# brobotESP12.net
KiCad netlist of a schematic drawn in EAGLE
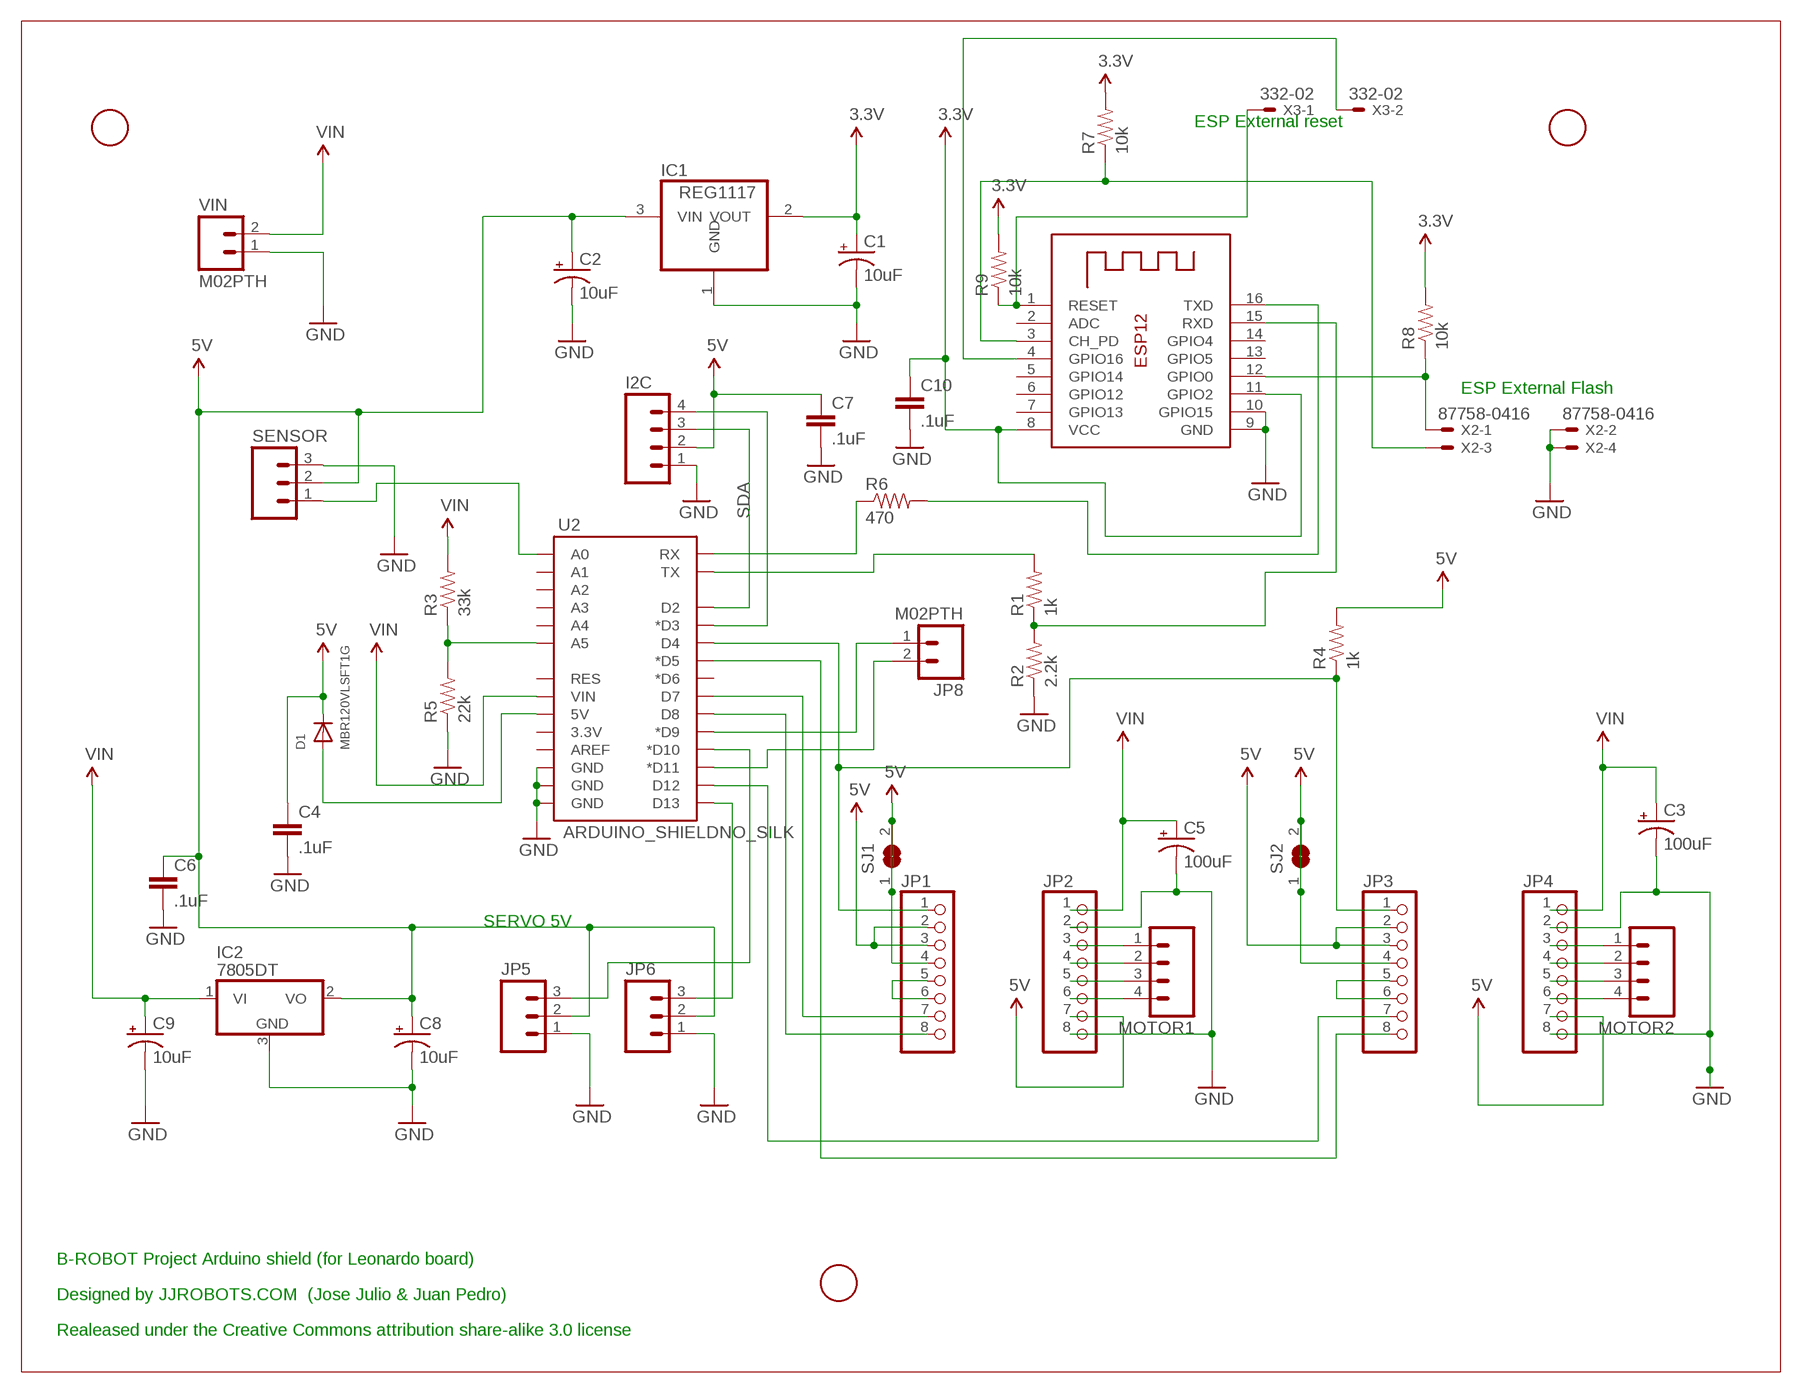
[diagram p0: schematic, sheet 1]

(export (version "E")
  (design (tool "Eeschema 10.0.6"))
  (components
    (comp (ref "C1")
      (value "10uF")
      (footprint "eagle-import:EIA3216")
      (libsource (lib "eagle-import") (part "CAP_POL1206"))
    )
    (comp (ref "C2")
      (value "10uF")
      (footprint "eagle-import:EIA3216")
      (libsource (lib "eagle-import") (part "CAP_POL1206"))
    )
    (comp (ref "C3")
      (value "100uF")
      (footprint "eagle-import:PANASONIC_D")
      (libsource (lib "eagle-import") (part "CAP_POLD"))
    )
    (comp (ref "C4")
      (value ".1uF")
      (footprint "eagle-import:0402-CAP")
      (libsource (lib "eagle-import") (part "CAP0402-CAP"))
    )
    (comp (ref "C5")
      (value "100uF")
      (footprint "eagle-import:PANASONIC_D")
      (libsource (lib "eagle-import") (part "CAP_POLD"))
    )
    (comp (ref "C6")
      (value ".1uF")
      (footprint "eagle-import:0402-CAP")
      (libsource (lib "eagle-import") (part "CAP0402-CAP"))
    )
    (comp (ref "C7")
      (value ".1uF")
      (footprint "eagle-import:0402-CAP")
      (libsource (lib "eagle-import") (part "CAP0402-CAP"))
    )
    (comp (ref "C8")
      (value "10uF")
      (footprint "eagle-import:EIA3216")
      (libsource (lib "eagle-import") (part "CAP_POL1206"))
    )
    (comp (ref "C9")
      (value "10uF")
      (footprint "eagle-import:EIA3216")
      (libsource (lib "eagle-import") (part "CAP_POL1206"))
    )
    (comp (ref "C10")
      (value ".1uF")
      (footprint "eagle-import:0402-CAP")
      (libsource (lib "eagle-import") (part "CAP0402-CAP"))
    )
    (comp (ref "D1")
      (value "MBR120VLSFT1G")
      (footprint "eagle-import:SOD-123")
      (libsource (lib "eagle-import") (part "DIODESOD-123"))
    )
    (comp (ref "I2C")
      (value "M04PTH")
      (footprint "eagle-import:1X04")
      (libsource (lib "eagle-import") (part "M04PTH"))
    )
    (comp (ref "IC1")
      (value "REG1117")
      (footprint "eagle-import:SOT223")
      (libsource (lib "eagle-import") (part "REG1117"))
    )
    (comp (ref "IC2")
      (value "7805DT")
      (footprint "eagle-import:TO252")
      (libsource (lib "eagle-import") (part "78DT05"))
    )
    (comp (ref "JP1")
      (value "PINHD-1X8")
      (footprint "eagle-import:1X08")
      (libsource (lib "eagle-import") (part "PINHD-1X8"))
    )
    (comp (ref "JP2")
      (value "PINHD-1X8")
      (footprint "eagle-import:1X08")
      (libsource (lib "eagle-import") (part "PINHD-1X8"))
    )
    (comp (ref "JP3")
      (value "PINHD-1X8")
      (footprint "eagle-import:1X08")
      (libsource (lib "eagle-import") (part "PINHD-1X8"))
    )
    (comp (ref "JP4")
      (value "PINHD-1X8")
      (footprint "eagle-import:1X08")
      (libsource (lib "eagle-import") (part "PINHD-1X8"))
    )
    (comp (ref "JP5")
      (value "M03PTH")
      (footprint "eagle-import:1X03")
      (libsource (lib "eagle-import") (part "M03PTH"))
    )
    (comp (ref "JP6")
      (value "M03PTH")
      (footprint "eagle-import:1X03")
      (libsource (lib "eagle-import") (part "M03PTH"))
    )
    (comp (ref "JP8")
      (value "M02PTH")
      (footprint "eagle-import:1X02")
      (libsource (lib "eagle-import") (part "M02PTH"))
    )
    (comp (ref "MOTOR1")
      (value "M04PTH")
      (footprint "eagle-import:1X04")
      (libsource (lib "eagle-import") (part "M04PTH"))
    )
    (comp (ref "MOTOR2")
      (value "M04PTH")
      (footprint "eagle-import:1X04")
      (libsource (lib "eagle-import") (part "M04PTH"))
    )
    (comp (ref "R1")
      (value "1k")
      (footprint "eagle-import:0805")
      (libsource (lib "eagle-import") (part "RESISTOR0805-RES"))
    )
    (comp (ref "R2")
      (value "2.2k")
      (footprint "eagle-import:0805")
      (libsource (lib "eagle-import") (part "RESISTOR0805-RES"))
    )
    (comp (ref "R3")
      (value "33k")
      (footprint "eagle-import:0805")
      (libsource (lib "eagle-import") (part "RESISTOR0805-RES"))
    )
    (comp (ref "R4")
      (value "1k")
      (footprint "eagle-import:0805")
      (libsource (lib "eagle-import") (part "RESISTOR0805-RES"))
    )
    (comp (ref "R5")
      (value "22k")
      (footprint "eagle-import:0805")
      (libsource (lib "eagle-import") (part "RESISTOR0805-RES"))
    )
    (comp (ref "R6")
      (value "470")
      (footprint "eagle-import:0805")
      (libsource (lib "eagle-import") (part "RESISTOR0805-RES"))
    )
    (comp (ref "R7")
      (value "10k")
      (footprint "eagle-import:0805")
      (libsource (lib "eagle-import") (part "RESISTOR0805-RES"))
    )
    (comp (ref "R8")
      (value "10k")
      (footprint "eagle-import:0805")
      (libsource (lib "eagle-import") (part "RESISTOR0805-RES"))
    )
    (comp (ref "R9")
      (value "10k")
      (footprint "eagle-import:0805")
      (libsource (lib "eagle-import") (part "RESISTOR0805-RES"))
    )
    (comp (ref "SENSOR")
      (value "M03PTH")
      (footprint "eagle-import:1X03")
      (libsource (lib "eagle-import") (part "M03PTH"))
    )
    (comp (ref "SJ1")
      (value "SJW")
      (footprint "eagle-import:SJW")
      (libsource (lib "eagle-import") (part "SJW"))
    )
    (comp (ref "SJ2")
      (value "SJW")
      (footprint "eagle-import:SJW")
      (libsource (lib "eagle-import") (part "SJW"))
    )
    (comp (ref "U$1")
      (value "FIDUCIAL")
      (footprint "eagle-import:FIDUCIAL_1MM")
      (libsource (lib "eagle-import") (part "FIDUCIAL"))
    )
    (comp (ref "U$2")
      (value "FIDUCIAL")
      (footprint "eagle-import:FIDUCIAL_1MM")
      (libsource (lib "eagle-import") (part "FIDUCIAL"))
    )
    (comp (ref "U$3")
      (value "FIDUCIAL")
      (footprint "eagle-import:FIDUCIAL_1MM")
      (libsource (lib "eagle-import") (part "FIDUCIAL"))
    )
    (comp (ref "U2")
      (value "ARDUINO_SHIELDNO_SILK")
      (footprint "eagle-import:DUEMILANOVE_VIAS")
      (libsource (lib "eagle-import") (part "ARDUINO_SHIELDNO_SILK"))
    )
    (comp (ref "VIN")
      (value "M02PTH")
      (footprint "eagle-import:1X02")
      (libsource (lib "eagle-import") (part "M02PTH"))
    )
    (comp (ref "X1")
      (value "ESP-12")
      (footprint "eagle-import:ESP-12")
      (libsource (lib "eagle-import") (part "ESP-12"))
    )
    (comp (ref "X2")
      (value "87758-0416")
      (footprint "eagle-import:87758-0416")
      (fields (field (name "MF") "FARNELL"))
      (libsource (lib "eagle-import") (part "87758-0416"))
    )
    (comp (ref "X3")
      (value "332-02")
      (footprint "eagle-import:332-02")
      (libsource (lib "eagle-import") (part "332-02"))
    )
  )
  (nets
    (net (code "1") (name "/SDA") (class "Default")
      (node (ref "I2C") (pin "3") (pinfunction "3_3") (pintype "passive"))
      (node (ref "U2") (pin "D2") (pinfunction "D2_D2") (pintype "bidirectional"))
    )
    (net (code "2") (name "3.3V") (class "Default")
      (node (ref "C1") (pin "A") (pinfunction "+_A") (pintype "passive"))
      (node (ref "C10") (pin "1") (pinfunction "1_1") (pintype "passive"))
      (node (ref "IC1") (pin "2") (pinfunction "VOUT_2") (pintype "output"))
      (node (ref "R7") (pin "2") (pinfunction "2_2") (pintype "passive"))
      (node (ref "R8") (pin "2") (pinfunction "2_2") (pintype "passive"))
      (node (ref "R9") (pin "2") (pinfunction "2_2") (pintype "passive"))
      (node (ref "X1") (pin "11") (pinfunction "GPIO2_11") (pintype "bidirectional"))
      (node (ref "X1") (pin "8") (pinfunction "VCC_8") (pintype "power_in"))
    )
    (net (code "3") (name "5V") (class "Default")
      (node (ref "C2") (pin "A") (pinfunction "+_A") (pintype "passive"))
      (node (ref "C4") (pin "1") (pinfunction "1_1") (pintype "passive"))
      (node (ref "C6") (pin "1") (pinfunction "1_1") (pintype "passive"))
      (node (ref "C7") (pin "1") (pinfunction "1_1") (pintype "passive"))
      (node (ref "C8") (pin "A") (pinfunction "+_A") (pintype "passive"))
      (node (ref "D1") (pin "C") (pinfunction "C_C") (pintype "passive"))
      (node (ref "I2C") (pin "2") (pinfunction "2_2") (pintype "passive"))
      (node (ref "IC1") (pin "3") (pinfunction "VIN_3") (pintype "input"))
      (node (ref "IC2") (pin "2") (pinfunction "VO_2") (pintype "passive"))
      (node (ref "JP1") (pin "2") (pinfunction "2_2") (pintype "passive"))
      (node (ref "JP1") (pin "3") (pinfunction "3_3") (pintype "passive"))
      (node (ref "JP1") (pin "4") (pinfunction "4_4") (pintype "passive"))
      (node (ref "JP2") (pin "7") (pinfunction "7_7") (pintype "passive"))
      (node (ref "JP3") (pin "2") (pinfunction "2_2") (pintype "passive"))
      (node (ref "JP3") (pin "3") (pinfunction "3_3") (pintype "passive"))
      (node (ref "JP3") (pin "4") (pinfunction "4_4") (pintype "passive"))
      (node (ref "JP4") (pin "7") (pinfunction "7_7") (pintype "passive"))
      (node (ref "JP5") (pin "2") (pinfunction "2_2") (pintype "passive"))
      (node (ref "JP6") (pin "2") (pinfunction "2_2") (pintype "passive"))
      (node (ref "R4") (pin "2") (pinfunction "2_2") (pintype "passive"))
      (node (ref "SENSOR") (pin "2") (pinfunction "2_2") (pintype "passive"))
      (node (ref "SJ1") (pin "1") (pinfunction "1_1") (pintype "passive"))
      (node (ref "SJ1") (pin "2") (pinfunction "2_2") (pintype "passive"))
      (node (ref "SJ2") (pin "1") (pinfunction "1_1") (pintype "passive"))
      (node (ref "SJ2") (pin "2") (pinfunction "2_2") (pintype "passive"))
    )
    (net (code "4") (name "GND") (class "Default")
      (node (ref "C1") (pin "C") (pinfunction "-_C") (pintype "passive"))
      (node (ref "C10") (pin "2") (pinfunction "2_2") (pintype "passive"))
      (node (ref "C2") (pin "C") (pinfunction "-_C") (pintype "passive"))
      (node (ref "C3") (pin "-") (pinfunction "-_-") (pintype "passive"))
      (node (ref "C4") (pin "2") (pinfunction "2_2") (pintype "passive"))
      (node (ref "C5") (pin "-") (pinfunction "-_-") (pintype "passive"))
      (node (ref "C6") (pin "2") (pinfunction "2_2") (pintype "passive"))
      (node (ref "C7") (pin "2") (pinfunction "2_2") (pintype "passive"))
      (node (ref "C8") (pin "C") (pinfunction "-_C") (pintype "passive"))
      (node (ref "C9") (pin "C") (pinfunction "-_C") (pintype "passive"))
      (node (ref "I2C") (pin "1") (pinfunction "1_1") (pintype "passive"))
      (node (ref "IC1") (pin "1") (pinfunction "GND_1") (pintype "power_in"))
      (node (ref "IC2") (pin "3") (pinfunction "GND_3") (pintype "passive"))
      (node (ref "JP2") (pin "2") (pinfunction "2_2") (pintype "passive"))
      (node (ref "JP2") (pin "8") (pinfunction "8_8") (pintype "passive"))
      (node (ref "JP4") (pin "2") (pinfunction "2_2") (pintype "passive"))
      (node (ref "JP4") (pin "8") (pinfunction "8_8") (pintype "passive"))
      (node (ref "JP5") (pin "1") (pinfunction "1_1") (pintype "passive"))
      (node (ref "JP6") (pin "1") (pinfunction "1_1") (pintype "passive"))
      (node (ref "R2") (pin "1") (pinfunction "1_1") (pintype "passive"))
      (node (ref "R5") (pin "1") (pinfunction "1_1") (pintype "passive"))
      (node (ref "SENSOR") (pin "3") (pinfunction "3_3") (pintype "passive"))
      (node (ref "U2") (pin "GND@0") (pinfunction "GND_GND@0") (pintype "bidirectional"))
      (node (ref "U2") (pin "GND@1") (pinfunction "GND_GND@1") (pintype "bidirectional"))
      (node (ref "U2") (pin "GND@2") (pinfunction "GND_GND@2") (pintype "bidirectional"))
      (node (ref "VIN") (pin "1") (pinfunction "1_1") (pintype "passive"))
      (node (ref "X1") (pin "10") (pinfunction "GPIO15_10") (pintype "bidirectional"))
      (node (ref "X1") (pin "9") (pinfunction "GND_9") (pintype "power_in"))
      (node (ref "X2") (pin "2") (pinfunction "S_2") (pintype "passive"))
      (node (ref "X2") (pin "4") (pinfunction "S_4") (pintype "passive"))
    )
    (net (code "5") (name "Net-(D1-PadA)") (class "Default")
      (node (ref "D1") (pin "A") (pinfunction "A_A") (pintype "passive"))
      (node (ref "U2") (pin "5V") (pinfunction "5V_5V") (pintype "bidirectional"))
    )
    (net (code "6") (name "Net-(JP1-Pad1)") (class "Default")
      (node (ref "JP1") (pin "1") (pinfunction "1_1") (pintype "passive"))
      (node (ref "JP3") (pin "1") (pinfunction "1_1") (pintype "passive"))
      (node (ref "R4") (pin "1") (pinfunction "1_1") (pintype "passive"))
      (node (ref "U2") (pin "D4") (pinfunction "D4_D4") (pintype "bidirectional"))
    )
    (net (code "7") (name "Net-(JP1-Pad5)") (class "Default")
      (node (ref "JP1") (pin "5") (pinfunction "5_5") (pintype "passive"))
      (node (ref "JP1") (pin "6") (pinfunction "6_6") (pintype "passive"))
    )
    (net (code "8") (name "Net-(JP1-Pad7)") (class "Default")
      (node (ref "JP1") (pin "7") (pinfunction "7_7") (pintype "passive"))
      (node (ref "U2") (pin "D7") (pinfunction "D7_D7") (pintype "bidirectional"))
    )
    (net (code "9") (name "Net-(JP1-Pad8)") (class "Default")
      (node (ref "JP1") (pin "8") (pinfunction "8_8") (pintype "passive"))
      (node (ref "U2") (pin "D8") (pinfunction "D8_D8") (pintype "bidirectional"))
    )
    (net (code "10") (name "Net-(JP2-Pad3)") (class "Default")
      (node (ref "JP2") (pin "3") (pinfunction "3_3") (pintype "passive"))
      (node (ref "MOTOR1") (pin "1") (pinfunction "1_1") (pintype "passive"))
    )
    (net (code "11") (name "Net-(JP2-Pad4)") (class "Default")
      (node (ref "JP2") (pin "4") (pinfunction "4_4") (pintype "passive"))
      (node (ref "MOTOR1") (pin "2") (pinfunction "2_2") (pintype "passive"))
    )
    (net (code "12") (name "Net-(JP2-Pad5)") (class "Default")
      (node (ref "JP2") (pin "5") (pinfunction "5_5") (pintype "passive"))
      (node (ref "MOTOR1") (pin "3") (pinfunction "3_3") (pintype "passive"))
    )
    (net (code "13") (name "Net-(JP2-Pad6)") (class "Default")
      (node (ref "JP2") (pin "6") (pinfunction "6_6") (pintype "passive"))
      (node (ref "MOTOR1") (pin "4") (pinfunction "4_4") (pintype "passive"))
    )
    (net (code "14") (name "Net-(JP3-Pad5)") (class "Default")
      (node (ref "JP3") (pin "5") (pinfunction "5_5") (pintype "passive"))
      (node (ref "JP3") (pin "6") (pinfunction "6_6") (pintype "passive"))
    )
    (net (code "15") (name "Net-(JP3-Pad7)") (class "Default")
      (node (ref "JP3") (pin "7") (pinfunction "7_7") (pintype "passive"))
      (node (ref "U2") (pin "D12") (pinfunction "D12_D12") (pintype "bidirectional"))
    )
    (net (code "16") (name "Net-(JP4-Pad3)") (class "Default")
      (node (ref "JP4") (pin "3") (pinfunction "3_3") (pintype "passive"))
      (node (ref "MOTOR2") (pin "1") (pinfunction "1_1") (pintype "passive"))
    )
    (net (code "17") (name "Net-(JP4-Pad4)") (class "Default")
      (node (ref "JP4") (pin "4") (pinfunction "4_4") (pintype "passive"))
      (node (ref "MOTOR2") (pin "2") (pinfunction "2_2") (pintype "passive"))
    )
    (net (code "18") (name "Net-(JP4-Pad5)") (class "Default")
      (node (ref "JP4") (pin "5") (pinfunction "5_5") (pintype "passive"))
      (node (ref "MOTOR2") (pin "3") (pinfunction "3_3") (pintype "passive"))
    )
    (net (code "19") (name "Net-(JP4-Pad6)") (class "Default")
      (node (ref "JP4") (pin "6") (pinfunction "6_6") (pintype "passive"))
      (node (ref "MOTOR2") (pin "4") (pinfunction "4_4") (pintype "passive"))
    )
    (net (code "20") (name "Net-(JP6-Pad3)") (class "Default")
      (node (ref "JP6") (pin "3") (pinfunction "3_3") (pintype "passive"))
      (node (ref "U2") (pin "D13") (pinfunction "D13_D13") (pintype "bidirectional"))
    )
    (net (code "21") (name "Net-(R1-Pad2)") (class "Default")
      (node (ref "R1") (pin "2") (pinfunction "2_2") (pintype "passive"))
      (node (ref "U2") (pin "TX") (pinfunction "TX_TX") (pintype "bidirectional"))
    )
    (net (code "22") (name "Net-(R3-Pad1)") (class "Default")
      (node (ref "R3") (pin "1") (pinfunction "1_1") (pintype "passive"))
      (node (ref "R5") (pin "2") (pinfunction "2_2") (pintype "passive"))
      (node (ref "U2") (pin "A5") (pinfunction "A5_A5") (pintype "bidirectional"))
    )
    (net (code "23") (name "Net-(R6-Pad1)") (class "Default")
      (node (ref "R6") (pin "1") (pinfunction "1_1") (pintype "passive"))
      (node (ref "U2") (pin "RX") (pinfunction "RX_RX") (pintype "bidirectional"))
    )
    (net (code "24") (name "Net-(SENSOR-Pad1)") (class "Default")
      (node (ref "SENSOR") (pin "1") (pinfunction "1_1") (pintype "passive"))
      (node (ref "U2") (pin "A0") (pinfunction "A0_A0") (pintype "bidirectional"))
    )
    (net (code "25") (name "Net-(U2-*D3)") (class "Default")
      (node (ref "I2C") (pin "4") (pinfunction "4_4") (pintype "passive"))
      (node (ref "U2") (pin "D3") (pinfunction "*D3_D3") (pintype "bidirectional"))
    )
    (net (code "26") (name "Net-(U2-*D5)") (class "Default")
      (node (ref "JP3") (pin "8") (pinfunction "8_8") (pintype "passive"))
      (node (ref "U2") (pin "D5") (pinfunction "*D5_D5") (pintype "bidirectional"))
    )
    (net (code "27") (name "Net-(U2-*D9)") (class "Default")
      (node (ref "JP8") (pin "1") (pinfunction "1_1") (pintype "passive"))
      (node (ref "U2") (pin "D9") (pinfunction "*D9_D9") (pintype "bidirectional"))
    )
    (net (code "28") (name "Net-(U2-*D10)") (class "Default")
      (node (ref "JP5") (pin "3") (pinfunction "3_3") (pintype "passive"))
      (node (ref "U2") (pin "D10") (pinfunction "*D10_D10") (pintype "bidirectional"))
    )
    (net (code "29") (name "Net-(U2-*D11)") (class "Default")
      (node (ref "JP8") (pin "2") (pinfunction "2_2") (pintype "passive"))
      (node (ref "U2") (pin "D11") (pinfunction "*D11_D11") (pintype "bidirectional"))
    )
    (net (code "30") (name "Net-(X1-CH_PD)") (class "Default")
      (node (ref "R7") (pin "1") (pinfunction "1_1") (pintype "passive"))
      (node (ref "X1") (pin "3") (pinfunction "CH_PD_3") (pintype "input"))
      (node (ref "X2") (pin "3") (pinfunction "S_3") (pintype "passive"))
    )
    (net (code "31") (name "Net-(X1-GPIO0)") (class "Default")
      (node (ref "R8") (pin "1") (pinfunction "1_1") (pintype "passive"))
      (node (ref "X1") (pin "12") (pinfunction "GPIO0_12") (pintype "bidirectional"))
      (node (ref "X2") (pin "1") (pinfunction "S_1") (pintype "passive"))
    )
    (net (code "32") (name "Net-(X1-GPIO16)") (class "Default")
      (node (ref "X1") (pin "4") (pinfunction "GPIO16_4") (pintype "bidirectional"))
      (node (ref "X3") (pin "2") (pinfunction "S_2") (pintype "passive"))
    )
    (net (code "33") (name "Net-(X1-RESET)") (class "Default")
      (node (ref "R9") (pin "1") (pinfunction "1_1") (pintype "passive"))
      (node (ref "X1") (pin "1") (pinfunction "RESET_1") (pintype "input"))
      (node (ref "X3") (pin "1") (pinfunction "S_1") (pintype "passive"))
    )
    (net (code "34") (name "Net-(X1-RXD)") (class "Default")
      (node (ref "R1") (pin "1") (pinfunction "1_1") (pintype "passive"))
      (node (ref "R2") (pin "2") (pinfunction "2_2") (pintype "passive"))
      (node (ref "X1") (pin "15") (pinfunction "RXD_15") (pintype "input"))
    )
    (net (code "35") (name "Net-(X1-TXD)") (class "Default")
      (node (ref "R6") (pin "2") (pinfunction "2_2") (pintype "passive"))
      (node (ref "X1") (pin "16") (pinfunction "TXD_16") (pintype "output"))
    )
    (net (code "36") (name "VIN") (class "Default")
      (node (ref "C3") (pin "+") (pinfunction "+_+") (pintype "passive"))
      (node (ref "C5") (pin "+") (pinfunction "+_+") (pintype "passive"))
      (node (ref "C9") (pin "A") (pinfunction "+_A") (pintype "passive"))
      (node (ref "IC2") (pin "1") (pinfunction "VI_1") (pintype "input"))
      (node (ref "JP2") (pin "1") (pinfunction "1_1") (pintype "passive"))
      (node (ref "JP4") (pin "1") (pinfunction "1_1") (pintype "passive"))
      (node (ref "R3") (pin "2") (pinfunction "2_2") (pintype "passive"))
      (node (ref "U2") (pin "VIN") (pinfunction "VIN_VIN") (pintype "bidirectional"))
      (node (ref "VIN") (pin "2") (pinfunction "2_2") (pintype "passive"))
    )
    (net (code "37") (name "unconnected-(U2-*D6-PadD6)") (class "Default")
      (node (ref "U2") (pin "D6") (pinfunction "*D6_D6") (pintype "bidirectional"))
    )
    (net (code "38") (name "unconnected-(U2-Pad3.3V)") (class "Default")
      (node (ref "U2") (pin "3.3V") (pinfunction "3.3V_3.3V") (pintype "bidirectional"))
    )
    (net (code "39") (name "unconnected-(U2-PadA1)") (class "Default")
      (node (ref "U2") (pin "A1") (pinfunction "A1_A1") (pintype "bidirectional"))
    )
    (net (code "40") (name "unconnected-(U2-PadA2)") (class "Default")
      (node (ref "U2") (pin "A2") (pinfunction "A2_A2") (pintype "bidirectional"))
    )
    (net (code "41") (name "unconnected-(U2-PadA3)") (class "Default")
      (node (ref "U2") (pin "A3") (pinfunction "A3_A3") (pintype "bidirectional"))
    )
    (net (code "42") (name "unconnected-(U2-PadA4)") (class "Default")
      (node (ref "U2") (pin "A4") (pinfunction "A4_A4") (pintype "bidirectional"))
    )
    (net (code "43") (name "unconnected-(U2-PadAREF)") (class "Default")
      (node (ref "U2") (pin "AREF") (pinfunction "AREF_AREF") (pintype "bidirectional"))
    )
    (net (code "44") (name "unconnected-(U2-PadRES)") (class "Default")
      (node (ref "U2") (pin "RES") (pinfunction "RES_RES") (pintype "bidirectional"))
    )
    (net (code "45") (name "unconnected-(X1-ADC-Pad2)") (class "Default")
      (node (ref "X1") (pin "2") (pinfunction "ADC_2") (pintype "passive"))
    )
    (net (code "46") (name "unconnected-(X1-GPIO4-Pad14)") (class "Default")
      (node (ref "X1") (pin "14") (pinfunction "GPIO4_14") (pintype "bidirectional"))
    )
    (net (code "47") (name "unconnected-(X1-GPIO5-Pad13)") (class "Default")
      (node (ref "X1") (pin "13") (pinfunction "GPIO5_13") (pintype "bidirectional"))
    )
    (net (code "48") (name "unconnected-(X1-GPIO12-Pad6)") (class "Default")
      (node (ref "X1") (pin "6") (pinfunction "GPIO12_6") (pintype "bidirectional"))
    )
    (net (code "49") (name "unconnected-(X1-GPIO13-Pad7)") (class "Default")
      (node (ref "X1") (pin "7") (pinfunction "GPIO13_7") (pintype "bidirectional"))
    )
    (net (code "50") (name "unconnected-(X1-GPIO14-Pad5)") (class "Default")
      (node (ref "X1") (pin "5") (pinfunction "GPIO14_5") (pintype "bidirectional"))
    )
  )
)
